# eVPS_Sensor.net
KiCad netlist of a schematic drawn in Altium Designer
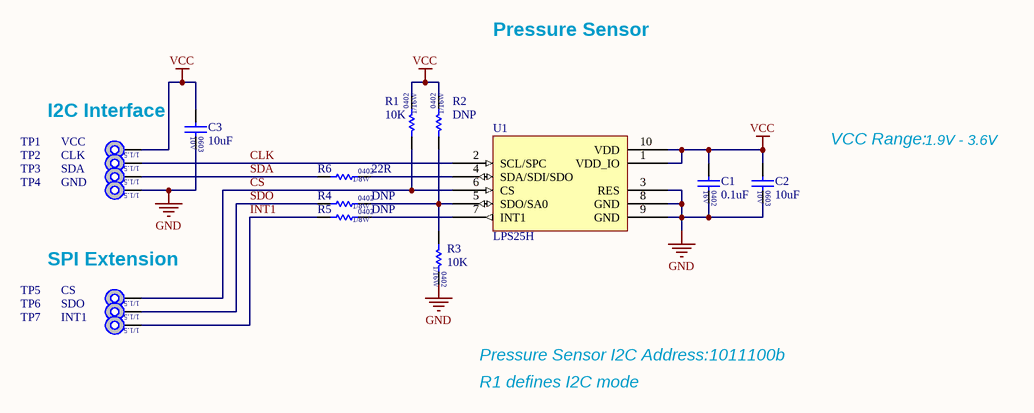
[diagram p0: eVPS_Sensor.SchDoc]

(export (version "E")
  (design (tool "Eeschema 10.0.6"))
  (components
    (comp (ref "C1")
      (value "0.1uF")
      (footprint "CAPC1005X60N")
      (description "CAP CER 0.1UF 0402 (1005) 16V X7R 10%")
      (fields (field (name "MANUFACTURER") "Murata Electronics North America"))
      (libsource (lib "ecoVENTPS") (part "Cap-1005 (0402) CER 0.1UF 16V X7R 10%"))
    )
    (comp (ref "C2")
      (value "10uF")
      (footprint "CAPC1608X95B")
      (description "Capacitor Ceramic 10uF 1608 (0603) 10V X5R 20%")
      (fields (field (name "MANUFACTURER") "Taiyo Yuden"))
      (libsource (lib "ecoVENTPS") (part "Cap-1608 (0603) CER 10uF 10V X5R 20%"))
    )
    (comp (ref "C3")
      (value "10uF")
      (footprint "CAPC1608X95B")
      (description "Capacitor Ceramic 10uF 1608 (0603) 10V X5R 20%")
      (fields (field (name "MANUFACTURER") "Taiyo Yuden"))
      (libsource (lib "ecoVENTPS") (part "Cap-1608 (0603) CER 10uF 10V X5R 20%"))
    )
    (comp (ref "R1")
      (value "10K")
      (footprint "RESC1005X40AN")
      (description "RES 10 KOhm 1/16W 1% 0402 SMD")
      (fields (field (name "MANUFACTURER") "Yageo"))
      (libsource (lib "ecoVENTPS") (part "Res-1005 (0402) 10 KOhm 1/16 1%"))
    )
    (comp (ref "R2")
      (value "DNP")
      (footprint "RESC1005X40AN")
      (description "RES 10 KOhm 1/16W 1% 0402 SMD")
      (fields (field (name "MANUFACTURER") "Yageo"))
      (libsource (lib "ecoVENTPS") (part "Res-1005 (0402) 10 KOhm 1/16 1%"))
    )
    (comp (ref "R3")
      (value "10K")
      (footprint "RESC1005X40AN")
      (description "RES 10 KOhm 1/16W 1% 0402 SMD")
      (fields (field (name "MANUFACTURER") "Yageo"))
      (libsource (lib "ecoVENTPS") (part "Res-1005 (0402) 10 KOhm 1/16 1%"))
    )
    (comp (ref "R4")
      (value "DNP")
      (footprint "RESC1005X40AN")
      (description "Res-1005 (0402) 22 Ohm 1/8W 1%")
      (fields (field (name "MANUFACTURER") "Vishay Dale"))
      (libsource (lib "ecoVENTPS") (part "Res-1005 (0402) 22 Ohm 1/8W 1%"))
    )
    (comp (ref "R5")
      (value "DNP")
      (footprint "RESC1005X40AN")
      (description "Res-1005 (0402) 22 Ohm 1/8W 1%")
      (fields (field (name "MANUFACTURER") "Vishay Dale"))
      (libsource (lib "ecoVENTPS") (part "Res-1005 (0402) 22 Ohm 1/8W 1%"))
    )
    (comp (ref "R6")
      (value "22R")
      (footprint "RESC1005X40AN")
      (description "Res-1005 (0402) 22 Ohm 1/8W 1%")
      (fields (field (name "MANUFACTURER") "Vishay Dale"))
      (libsource (lib "ecoVENTPS") (part "Res-1005 (0402) 22 Ohm 1/8W 1%"))
    )
    (comp (ref "TP1")
      (value "VCC")
      (footprint "TEST_POINT_TH_1.5MM")
      (description "Test point Through Hole")
      (libsource (lib "ecoVENTPS") (part "TP TH 1X1.5mm"))
    )
    (comp (ref "TP2")
      (value "CLK")
      (footprint "TEST_POINT_TH_1.5MM")
      (description "Test point Through Hole")
      (libsource (lib "ecoVENTPS") (part "TP TH 1X1.5mm"))
    )
    (comp (ref "TP3")
      (value "SDA")
      (footprint "TEST_POINT_TH_1.5MM")
      (description "Test point Through Hole")
      (libsource (lib "ecoVENTPS") (part "TP TH 1X1.5mm"))
    )
    (comp (ref "TP4")
      (value "GND")
      (footprint "TEST_POINT_TH_1.5MM")
      (description "Test point Through Hole")
      (libsource (lib "ecoVENTPS") (part "TP TH 1X1.5mm"))
    )
    (comp (ref "TP5")
      (value "CS")
      (footprint "TEST_POINT_TH_1.5MM")
      (description "Test point Through Hole")
      (libsource (lib "ecoVENTPS") (part "TP TH 1X1.5mm"))
    )
    (comp (ref "TP6")
      (value "SDO")
      (footprint "TEST_POINT_TH_1.5MM")
      (description "Test point Through Hole")
      (libsource (lib "ecoVENTPS") (part "TP TH 1X1.5mm"))
    )
    (comp (ref "TP7")
      (value "INT1")
      (footprint "TEST_POINT_TH_1.5MM")
      (description "Test point Through Hole")
      (libsource (lib "ecoVENTPS") (part "TP TH 1X1.5mm"))
    )
    (comp (ref "U1")
      (value "LPS25H")
      (footprint "STM_HCLGA10L")
      (description "MEMS Pressure Sensor")
      (fields (field (name "MANUFACTURER") "ST Microelectronics"))
      (libsource (lib "ecoVENTPS") (part "LPS25H"))
    )
  )
  (nets
    (net (code "1") (name "/CLK") (class "Default")
      (node (ref "TP2") (pin "1") (pinfunction "1_1") (pintype "passive"))
      (node (ref "U1") (pin "2") (pinfunction "SCL/SPC_2") (pintype "input"))
    )
    (net (code "2") (name "/CS") (class "Default")
      (node (ref "R1") (pin "1") (pinfunction "1_1") (pintype "passive"))
      (node (ref "TP5") (pin "1") (pinfunction "1_1") (pintype "passive"))
      (node (ref "U1") (pin "6") (pinfunction "CS_6") (pintype "input"))
    )
    (net (code "3") (name "/INT1") (class "Default")
      (node (ref "R5") (pin "2") (pinfunction "2_2") (pintype "passive"))
      (node (ref "TP7") (pin "1") (pinfunction "1_1") (pintype "passive"))
    )
    (net (code "4") (name "/SDA") (class "Default")
      (node (ref "R6") (pin "2") (pinfunction "2_2") (pintype "passive"))
      (node (ref "TP3") (pin "1") (pinfunction "1_1") (pintype "passive"))
    )
    (net (code "5") (name "/SDO") (class "Default")
      (node (ref "R4") (pin "2") (pinfunction "2_2") (pintype "passive"))
      (node (ref "TP6") (pin "1") (pinfunction "1_1") (pintype "passive"))
    )
    (net (code "6") (name "GND") (class "Default")
      (node (ref "C1") (pin "2") (pinfunction "2_2") (pintype "passive"))
      (node (ref "C2") (pin "2") (pinfunction "2_2") (pintype "passive"))
      (node (ref "C3") (pin "2") (pinfunction "2_2") (pintype "passive"))
      (node (ref "R3") (pin "2") (pinfunction "2_2") (pintype "passive"))
      (node (ref "TP4") (pin "1") (pinfunction "1_1") (pintype "passive"))
      (node (ref "U1") (pin "3") (pinfunction "RES_3") (pintype "passive"))
      (node (ref "U1") (pin "8") (pinfunction "GND_8") (pintype "power_in"))
      (node (ref "U1") (pin "9") (pinfunction "GND_9") (pintype "power_in"))
    )
    (net (code "7") (name "Net-(U1-INT1)") (class "Default")
      (node (ref "R5") (pin "1") (pinfunction "1_1") (pintype "passive"))
      (node (ref "U1") (pin "7") (pinfunction "INT1_7") (pintype "output"))
    )
    (net (code "8") (name "Net-(U1-SDA{slash}SDI{slash}SDO)") (class "Default")
      (node (ref "R6") (pin "1") (pinfunction "1_1") (pintype "passive"))
      (node (ref "U1") (pin "4") (pinfunction "SDA/SDI/SDO_4") (pintype "bidirectional"))
    )
    (net (code "9") (name "Net-(U1-SDO{slash}SA0)") (class "Default")
      (node (ref "R2") (pin "1") (pinfunction "1_1") (pintype "passive"))
      (node (ref "R3") (pin "1") (pinfunction "1_1") (pintype "passive"))
      (node (ref "R4") (pin "1") (pinfunction "1_1") (pintype "passive"))
      (node (ref "U1") (pin "5") (pinfunction "SDO/SA0_5") (pintype "bidirectional"))
    )
    (net (code "10") (name "VCC") (class "Default")
      (node (ref "C1") (pin "1") (pinfunction "1_1") (pintype "passive"))
      (node (ref "C2") (pin "1") (pinfunction "1_1") (pintype "passive"))
      (node (ref "C3") (pin "1") (pinfunction "1_1") (pintype "passive"))
      (node (ref "R1") (pin "2") (pinfunction "2_2") (pintype "passive"))
      (node (ref "R2") (pin "2") (pinfunction "2_2") (pintype "passive"))
      (node (ref "TP1") (pin "1") (pinfunction "1_1") (pintype "passive"))
      (node (ref "U1") (pin "1") (pinfunction "VDD_IO_1") (pintype "power_in"))
      (node (ref "U1") (pin "10") (pinfunction "VDD_10") (pintype "power_in"))
    )
  )
)
